# Supply.net
KiCad netlist of a schematic drawn in Altium Designer
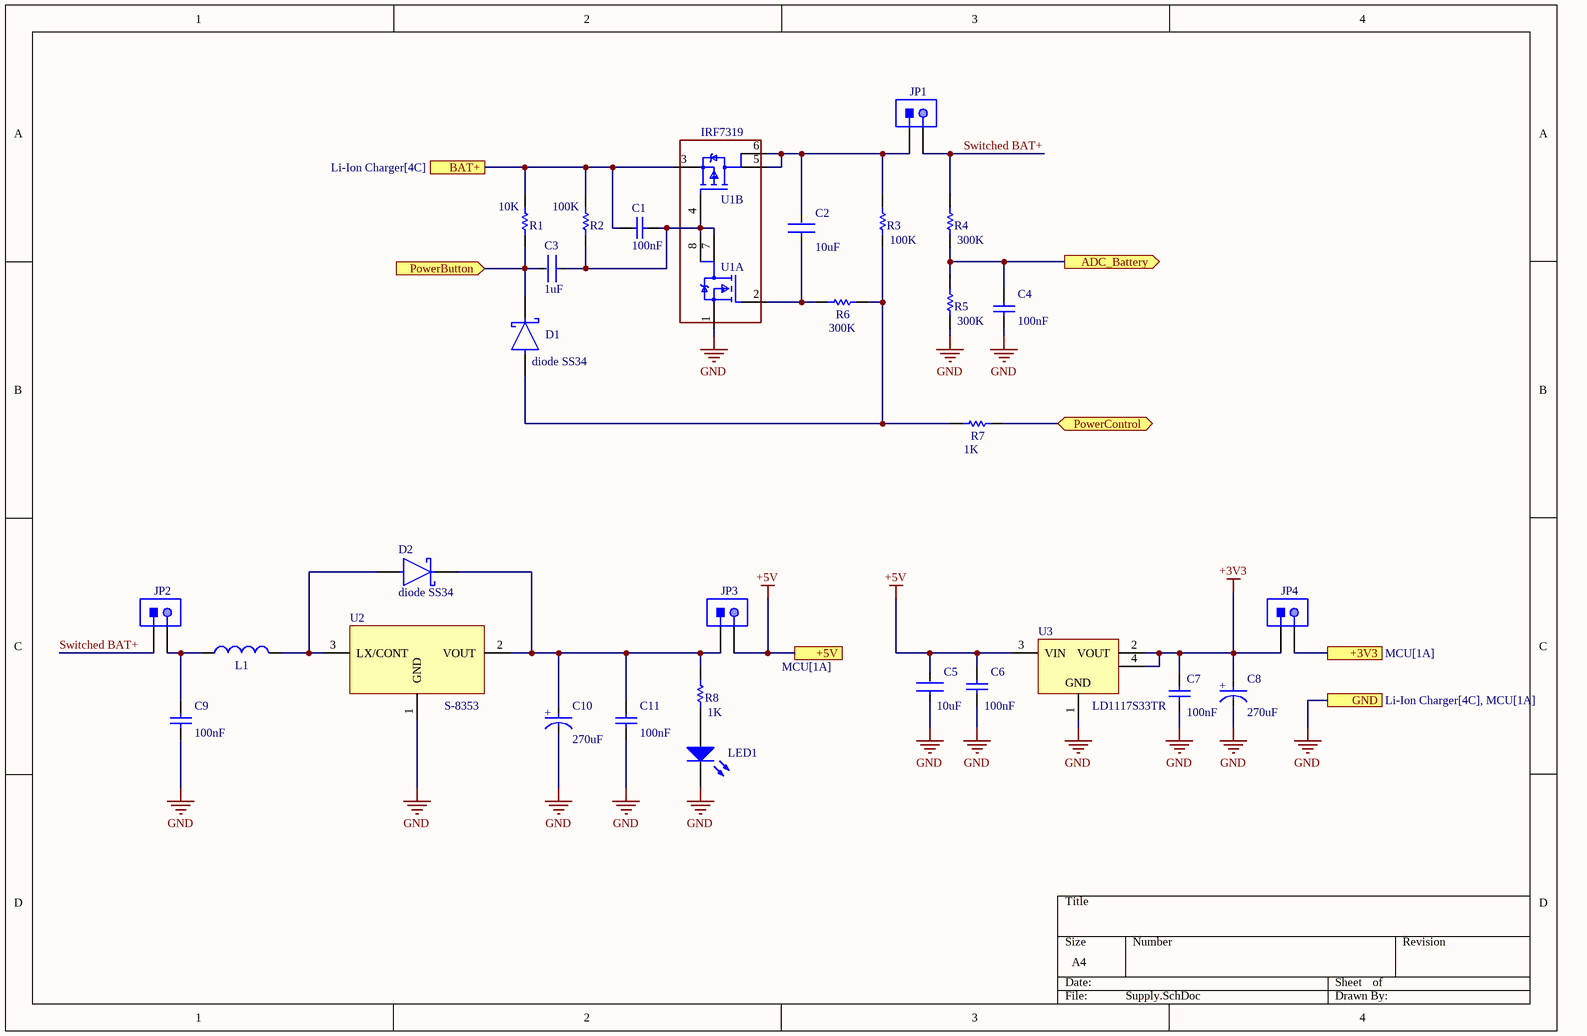
[diagram p0: Supply.SchDoc]

(export (version "E")
  (design (tool "Eeschema 10.0.6"))
  (components
    (comp (ref "C1")
      (value "100nF")
      (footprint "CAPC2013X140X50LL20T25")
      (description "Cap Ceramic 0.1uF 50V X7R 10% Pad SMD 0805 FlexiTerm 125C Automotive T/R")
      (fields (field (name "Comment") "capacitor smd 0805 100nF"))
      (libsource (lib "Lotnicza Akademia Wojskowa") (part "CAP"))
    )
    (comp (ref "C2")
      (value "10uF")
      (footprint "FP-GRM31-0_2-IPC_B")
      (description "Multilayer Ceramic Capacitors MLCC - SMD/SMT 1206 10uF 50volt X5R +/-10%")
      (fields (field (name "Comment") "capacitor smd 1206 10uF"))
      (libsource (lib "Lotnicza Akademia Wojskowa") (part "11868f565c42a9108669ba33697ecf6"))
    )
    (comp (ref "C3")
      (value "1uF")
      (footprint "FP-GRM31-0_2-IPC_B")
      (description "Multilayer Ceramic Capacitors MLCC - SMD/SMT 1206 10uF 50volt X5R +/-10%")
      (fields (field (name "Comment") "capacitor smd 1206 10uF"))
      (libsource (lib "Lotnicza Akademia Wojskowa") (part "11868f565c42a9108669ba33697ecf6"))
    )
    (comp (ref "C4")
      (value "100nF")
      (footprint "CAPC2013X140X50LL20T25")
      (description "Cap Ceramic 0.1uF 50V X7R 10% Pad SMD 0805 FlexiTerm 125C Automotive T/R")
      (fields (field (name "Comment") "capacitor smd 0805 100nF"))
      (libsource (lib "Lotnicza Akademia Wojskowa") (part "CAP"))
    )
    (comp (ref "C5")
      (value "10uF")
      (footprint "FP-GRM31-0_2-IPC_B")
      (description "Multilayer Ceramic Capacitors MLCC - SMD/SMT 1206 10uF 50volt X5R +/-10%")
      (fields (field (name "Comment") "capacitor smd 1206 10uF"))
      (libsource (lib "Lotnicza Akademia Wojskowa") (part "11868f565c42a9108669ba33697ecf6"))
    )
    (comp (ref "C6")
      (value "100nF")
      (footprint "CAPC2013X140X50LL20T25")
      (description "Cap Ceramic 0.1uF 50V X7R 10% Pad SMD 0805 FlexiTerm 125C Automotive T/R")
      (fields (field (name "Comment") "capacitor smd 0805 100nF"))
      (libsource (lib "Lotnicza Akademia Wojskowa") (part "CAP"))
    )
    (comp (ref "C7")
      (value "100nF")
      (footprint "CAPC2013X140X50LL20T25")
      (description "Cap Ceramic 0.1uF 50V X7R 10% Pad SMD 0805 FlexiTerm 125C Automotive T/R")
      (fields (field (name "Comment") "capacitor smd 0805 100nF"))
      (libsource (lib "Lotnicza Akademia Wojskowa") (part "CAP"))
    )
    (comp (ref "C8")
      (value "270uF")
      (footprint "FP-OS-CON-TH-E12-d_0_6-MFG")
      (description "Cap Aluminum Polymer 270uF 16VDC 20% (8 X 12mm) Radial 3.5mm 0.011 Ohm 5000mA 5000h 105C T/R")
      (fields (field (name "Comment") "capacitor 270uF 16V"))
      (libsource (lib "Lotnicza Akademia Wojskowa") (part "203bc49f2ac43e59fd269a8c329ed05"))
    )
    (comp (ref "C9")
      (value "100nF")
      (footprint "CAPC2013X140X50LL20T25")
      (description "Cap Ceramic 0.1uF 50V X7R 10% Pad SMD 0805 FlexiTerm 125C Automotive T/R")
      (fields (field (name "Comment") "capacitor smd 0805 100nF"))
      (libsource (lib "Lotnicza Akademia Wojskowa") (part "CAP"))
    )
    (comp (ref "C10")
      (value "270uF")
      (footprint "FP-OS-CON-TH-E12-d_0_6-MFG")
      (description "Cap Aluminum Polymer 270uF 16VDC 20% (8 X 12mm) Radial 3.5mm 0.011 Ohm 5000mA 5000h 105C T/R")
      (fields (field (name "Comment") "capacitor 270uF 16V"))
      (libsource (lib "Lotnicza Akademia Wojskowa") (part "203bc49f2ac43e59fd269a8c329ed05"))
    )
    (comp (ref "C11")
      (value "100nF")
      (footprint "CAPC2013X140X50LL20T25")
      (description "Cap Ceramic 0.1uF 50V X7R 10% Pad SMD 0805 FlexiTerm 125C Automotive T/R")
      (fields (field (name "Comment") "capacitor smd 0805 100nF"))
      (libsource (lib "Lotnicza Akademia Wojskowa") (part "CAP"))
    )
    (comp (ref "D1")
      (value "diode SS34")
      (footprint "FP-SS34LWH-MFG")
      (description "Rectifier Diode Schottky 40V 3A Automotive 2-Pin SOD-123W T/R")
      (libsource (lib "Lotnicza Akademia Wojskowa") (part "1d6ec82d83fb6aee721767c19dac4b9"))
    )
    (comp (ref "D2")
      (value "diode SS34")
      (footprint "FP-SS34LWH-MFG")
      (description "Rectifier Diode Schottky 40V 3A Automotive 2-Pin SOD-123W T/R")
      (libsource (lib "Lotnicza Akademia Wojskowa") (part "1d6ec82d83fb6aee721767c19dac4b9"))
    )
    (comp (ref "JP1")
      (value "header 2.54 2pin")
      (footprint "61300211121")
      (description "CONN HEADER 2 POS 2.54")
      (libsource (lib "Lotnicza Akademia Wojskowa") (part "WE-CN-1P-M-R2"))
    )
    (comp (ref "JP2")
      (value "header 2.54 2pin")
      (footprint "61300211121")
      (description "CONN HEADER 2 POS 2.54")
      (libsource (lib "Lotnicza Akademia Wojskowa") (part "WE-CN-1P-M-R2"))
    )
    (comp (ref "JP3")
      (value "header 2.54 2pin")
      (footprint "61300211121")
      (description "CONN HEADER 2 POS 2.54")
      (libsource (lib "Lotnicza Akademia Wojskowa") (part "WE-CN-1P-M-R2"))
    )
    (comp (ref "JP4")
      (value "header 2.54 2pin")
      (footprint "61300211121")
      (description "CONN HEADER 2 POS 2.54")
      (libsource (lib "Lotnicza Akademia Wojskowa") (part "WE-CN-1P-M-R2"))
    )
    (comp (ref "L1")
      (value "power inductor 470uH")
      (footprint "WE-PD4-S")
      (libsource (lib "Lotnicza Akademia Wojskowa") (part "PAS-IND-INDUCTOR-2"))
    )
    (comp (ref "LED1")
      (value "LED green 0805")
      (footprint "0805_A")
      (description "Led, Green, 520 Nm, 3.2 V, 30 Ma, 450 Mcd Rohs Compliant: Yes")
      (libsource (lib "Lotnicza Akademia Wojskowa") (part "WE-LED_K1A2-2"))
    )
    (comp (ref "R1")
      (value "10K")
      (footprint "RESC2013X50X30ML20T20")
      (description "Res Thick Film 0805 1K Ohm 1% 1/8W ±100ppm/°C Molded SMD Paper T/R")
      (fields (field (name "Comment") "resistor smd 0805 1K"))
      (libsource (lib "Lotnicza Akademia Wojskowa") (part "RES"))
    )
    (comp (ref "R2")
      (value "100K")
      (footprint "RESC2013X50X30ML20T20")
      (description "Res Thick Film 0805 1K Ohm 1% 1/8W ±100ppm/°C Molded SMD Paper T/R")
      (fields (field (name "Comment") "resistor smd 0805 1K"))
      (libsource (lib "Lotnicza Akademia Wojskowa") (part "RES"))
    )
    (comp (ref "R3")
      (value "100K")
      (footprint "RESC2013X50X30ML20T20")
      (description "Res Thick Film 0805 1K Ohm 1% 1/8W ±100ppm/°C Molded SMD Paper T/R")
      (fields (field (name "Comment") "resistor smd 0805 1K"))
      (libsource (lib "Lotnicza Akademia Wojskowa") (part "RES"))
    )
    (comp (ref "R4")
      (value "300K")
      (footprint "RESC2013X50X30ML20T20")
      (description "Res Thick Film 0805 1K Ohm 1% 1/8W ±100ppm/°C Molded SMD Paper T/R")
      (fields (field (name "Comment") "resistor smd 0805 1K"))
      (libsource (lib "Lotnicza Akademia Wojskowa") (part "RES"))
    )
    (comp (ref "R5")
      (value "300K")
      (footprint "RESC2013X50X30ML20T20")
      (description "Res Thick Film 0805 1K Ohm 1% 1/8W ±100ppm/°C Molded SMD Paper T/R")
      (fields (field (name "Comment") "resistor smd 0805 1K"))
      (libsource (lib "Lotnicza Akademia Wojskowa") (part "RES"))
    )
    (comp (ref "R6")
      (value "300K")
      (footprint "RESC2013X50X30ML20T20")
      (description "Res Thick Film 0805 1K Ohm 1% 1/8W ±100ppm/°C Molded SMD Paper T/R")
      (fields (field (name "Comment") "resistor smd 0805 1K"))
      (libsource (lib "Lotnicza Akademia Wojskowa") (part "RES"))
    )
    (comp (ref "R7")
      (value "1K")
      (footprint "RESC2013X50X30ML20T20")
      (description "Res Thick Film 0805 1K Ohm 1% 1/8W ±100ppm/°C Molded SMD Paper T/R")
      (fields (field (name "Comment") "resistor smd 0805 1K"))
      (libsource (lib "Lotnicza Akademia Wojskowa") (part "RES"))
    )
    (comp (ref "R8")
      (value "1K")
      (footprint "RESC2013X50X30ML20T20")
      (description "Res Thick Film 0805 1K Ohm 1% 1/8W ±100ppm/°C Molded SMD Paper T/R")
      (fields (field (name "Comment") "resistor smd 0805 1K"))
      (libsource (lib "Lotnicza Akademia Wojskowa") (part "RES"))
    )
    (comp (ref "U1")
      (value "IRF7319")
      (footprint "FP-PG-DSO-8-IPC_B")
      (description "IRF7309PBF Dual N/P-channel MOSFET Transistor; 3 A; 4 A; 30 V; 8-Pin SOIC")
      (libsource (lib "Lotnicza Akademia Wojskowa") (part "d515b9fab8fe3318af14a28d53c5fd4"))
    )
    (comp (ref "U2")
      (value "S-8353")
      (footprint "SOT89-150P410X160-3N")
      (libsource (lib "Lotnicza Akademia Wojskowa") (part "S-8353"))
    )
    (comp (ref "U3")
      (value "LD1117S33TR")
      (footprint "SOT-223_L")
      (description "IC REG LDO 3.3V 0.8A SOT223")
      (libsource (lib "Lotnicza Akademia Wojskowa") (part "PM-REG-LD1117-SOT4"))
    )
  )
  (nets
    (net (code "1") (name "+3V3") (class "Default")
      (node (ref "C7") (pin "2") (pinfunction "2_2") (pintype "passive"))
      (node (ref "C8") (pin "2") (pinfunction "A_2") (pintype "passive"))
      (node (ref "JP4") (pin "1") (pinfunction "1_1") (pintype "passive"))
      (node (ref "JP4") (pin "2") (pinfunction "2_2") (pintype "passive"))
      (node (ref "U3") (pin "2") (pinfunction "VOUT_2") (pintype "power_in"))
      (node (ref "U3") (pin "4") (pinfunction "VOUT_4") (pintype "power_in"))
    )
    (net (code "2") (name "+5V") (class "Default")
      (node (ref "C5") (pin "2") (pinfunction "2_2") (pintype "passive"))
      (node (ref "C6") (pin "2") (pinfunction "2_2") (pintype "passive"))
      (node (ref "JP3") (pin "2") (pinfunction "2_2") (pintype "passive"))
      (node (ref "U3") (pin "3") (pinfunction "VIN_3") (pintype "power_in"))
    )
    (net (code "3") (name "/ADC_Battery") (class "Default")
      (node (ref "C4") (pin "2") (pinfunction "2_2") (pintype "passive"))
      (node (ref "R4") (pin "1") (pinfunction "1_1") (pintype "passive"))
      (node (ref "R5") (pin "2") (pinfunction "2_2") (pintype "passive"))
    )
    (net (code "4") (name "/BAT+") (class "Default")
      (node (ref "C1") (pin "2") (pinfunction "2_2") (pintype "passive"))
      (node (ref "R1") (pin "2") (pinfunction "2_2") (pintype "passive"))
      (node (ref "R2") (pin "2") (pinfunction "2_2") (pintype "passive"))
      (node (ref "U1") (pin "3") (pinfunction "S2_3") (pintype "passive"))
    )
    (net (code "5") (name "/PowerButton") (class "Default")
      (node (ref "C3") (pin "2") (pinfunction "2_2") (pintype "passive"))
      (node (ref "D1") (pin "1") (pinfunction "C_1") (pintype "passive"))
      (node (ref "R1") (pin "1") (pinfunction "1_1") (pintype "passive"))
    )
    (net (code "6") (name "/PowerControl") (class "Default")
      (node (ref "R7") (pin "2") (pinfunction "2_2") (pintype "passive"))
    )
    (net (code "7") (name "/Switched BAT+") (class "Default")
      (node (ref "JP1") (pin "2") (pinfunction "2_2") (pintype "passive"))
      (node (ref "JP2") (pin "1") (pinfunction "1_1") (pintype "passive"))
      (node (ref "R4") (pin "2") (pinfunction "2_2") (pintype "passive"))
    )
    (net (code "8") (name "GND") (class "Default")
      (node (ref "C10") (pin "1") (pinfunction "C_1") (pintype "passive"))
      (node (ref "C11") (pin "1") (pinfunction "1_1") (pintype "passive"))
      (node (ref "C4") (pin "1") (pinfunction "1_1") (pintype "passive"))
      (node (ref "C5") (pin "1") (pinfunction "1_1") (pintype "passive"))
      (node (ref "C6") (pin "1") (pinfunction "1_1") (pintype "passive"))
      (node (ref "C7") (pin "1") (pinfunction "1_1") (pintype "passive"))
      (node (ref "C8") (pin "1") (pinfunction "C_1") (pintype "passive"))
      (node (ref "C9") (pin "1") (pinfunction "1_1") (pintype "passive"))
      (node (ref "LED1") (pin "1") (pinfunction "K_1") (pintype "passive"))
      (node (ref "R5") (pin "1") (pinfunction "1_1") (pintype "passive"))
      (node (ref "U1") (pin "1") (pinfunction "S1_1") (pintype "passive"))
      (node (ref "U2") (pin "1") (pinfunction "GND_1") (pintype "power_in"))
      (node (ref "U3") (pin "1") (pinfunction "GND_1") (pintype "power_in"))
    )
    (net (code "9") (name "Net-(C2-Pad2)") (class "Default")
      (node (ref "C2") (pin "2") (pinfunction "2_2") (pintype "passive"))
      (node (ref "JP1") (pin "1") (pinfunction "1_1") (pintype "passive"))
      (node (ref "R3") (pin "2") (pinfunction "2_2") (pintype "passive"))
      (node (ref "U1") (pin "5") (pinfunction "D2_5") (pintype "passive"))
      (node (ref "U1") (pin "6") (pinfunction "D2_6") (pintype "passive"))
    )
    (net (code "10") (name "Net-(C9-Pad2)") (class "Default")
      (node (ref "C9") (pin "2") (pinfunction "2_2") (pintype "passive"))
      (node (ref "JP2") (pin "2") (pinfunction "2_2") (pintype "passive"))
      (node (ref "L1") (pin "1") (pinfunction "1_1") (pintype "passive"))
    )
    (net (code "11") (name "Net-(C10-A)") (class "Default")
      (node (ref "C10") (pin "2") (pinfunction "A_2") (pintype "passive"))
      (node (ref "C11") (pin "2") (pinfunction "2_2") (pintype "passive"))
      (node (ref "D2") (pin "1") (pinfunction "C_1") (pintype "passive"))
      (node (ref "JP3") (pin "1") (pinfunction "1_1") (pintype "passive"))
      (node (ref "R8") (pin "2") (pinfunction "2_2") (pintype "passive"))
      (node (ref "U2") (pin "2") (pinfunction "VOUT_2") (pintype "passive"))
    )
    (net (code "12") (name "Net-(D1-A)") (class "Default")
      (node (ref "D1") (pin "2") (pinfunction "A_2") (pintype "passive"))
      (node (ref "R3") (pin "1") (pinfunction "1_1") (pintype "passive"))
      (node (ref "R6") (pin "2") (pinfunction "2_2") (pintype "passive"))
      (node (ref "R7") (pin "1") (pinfunction "1_1") (pintype "passive"))
    )
    (net (code "13") (name "Net-(D2-A)") (class "Default")
      (node (ref "D2") (pin "2") (pinfunction "A_2") (pintype "passive"))
      (node (ref "L1") (pin "2") (pinfunction "2_2") (pintype "passive"))
      (node (ref "U2") (pin "3") (pinfunction "LX/CONT_3") (pintype "passive"))
    )
    (net (code "14") (name "Net-(LED1-A)") (class "Default")
      (node (ref "LED1") (pin "2") (pinfunction "A_2") (pintype "passive"))
      (node (ref "R8") (pin "1") (pinfunction "1_1") (pintype "passive"))
    )
    (net (code "15") (name "Net-(U1A-G1)") (class "Default")
      (node (ref "C2") (pin "1") (pinfunction "1_1") (pintype "passive"))
      (node (ref "R6") (pin "1") (pinfunction "1_1") (pintype "passive"))
      (node (ref "U1") (pin "2") (pinfunction "G1_2") (pintype "passive"))
    )
    (net (code "16") (name "Net-(U1B-G2)") (class "Default")
      (node (ref "C1") (pin "1") (pinfunction "1_1") (pintype "passive"))
      (node (ref "C3") (pin "1") (pinfunction "1_1") (pintype "passive"))
      (node (ref "R2") (pin "1") (pinfunction "1_1") (pintype "passive"))
      (node (ref "U1") (pin "4") (pinfunction "G2_4") (pintype "passive"))
      (node (ref "U1") (pin "7") (pinfunction "D1_7") (pintype "passive"))
      (node (ref "U1") (pin "8") (pinfunction "D1_8") (pintype "passive"))
    )
  )
)
